# 04-ANDStatusLed.net
KiCad netlist of a schematic drawn in Altium Designer
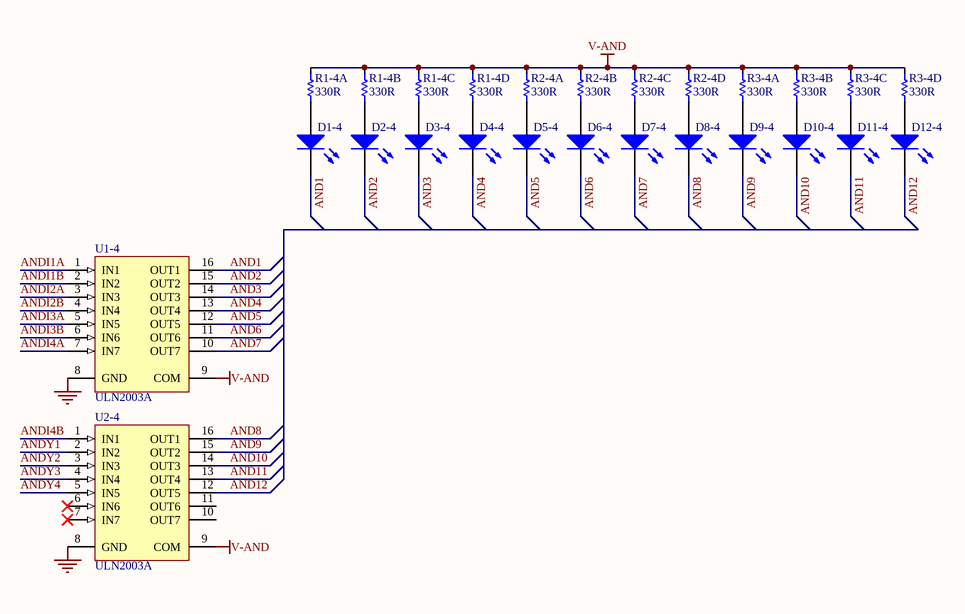
[diagram p0: 04-ANDStatusLed.SchDoc]

(export (version "E")
  (design (tool "Eeschema 10.0.6"))
  (components
    (comp (ref "D1-4")
      (value "LED")
      (footprint "LED-0805")
      (description "Typical RED, GREEN, YELLOW, AMBER GaAs LED")
      (fields (field (name "PUBLISHER") "Altium Limited"))
      (libsource (lib "Miscellaneous Devices") (part "LED2"))
    )
    (comp (ref "D2-4")
      (value "LED")
      (footprint "LED-0805")
      (description "Typical RED, GREEN, YELLOW, AMBER GaAs LED")
      (fields (field (name "PUBLISHER") "Altium Limited"))
      (libsource (lib "Miscellaneous Devices") (part "LED2"))
    )
    (comp (ref "D3-4")
      (value "LED")
      (footprint "LED-0805")
      (description "Typical RED, GREEN, YELLOW, AMBER GaAs LED")
      (fields (field (name "PUBLISHER") "Altium Limited"))
      (libsource (lib "Miscellaneous Devices") (part "LED2"))
    )
    (comp (ref "D4-4")
      (value "LED")
      (footprint "LED-0805")
      (description "Typical RED, GREEN, YELLOW, AMBER GaAs LED")
      (fields (field (name "PUBLISHER") "Altium Limited"))
      (libsource (lib "Miscellaneous Devices") (part "LED2"))
    )
    (comp (ref "D5-4")
      (value "LED")
      (footprint "LED-0805")
      (description "Typical RED, GREEN, YELLOW, AMBER GaAs LED")
      (fields (field (name "PUBLISHER") "Altium Limited"))
      (libsource (lib "Miscellaneous Devices") (part "LED2"))
    )
    (comp (ref "D6-4")
      (value "LED")
      (footprint "LED-0805")
      (description "Typical RED, GREEN, YELLOW, AMBER GaAs LED")
      (fields (field (name "PUBLISHER") "Altium Limited"))
      (libsource (lib "Miscellaneous Devices") (part "LED2"))
    )
    (comp (ref "D7-4")
      (value "LED")
      (footprint "LED-0805")
      (description "Typical RED, GREEN, YELLOW, AMBER GaAs LED")
      (fields (field (name "PUBLISHER") "Altium Limited"))
      (libsource (lib "Miscellaneous Devices") (part "LED2"))
    )
    (comp (ref "D8-4")
      (value "LED")
      (footprint "LED-0805")
      (description "Typical RED, GREEN, YELLOW, AMBER GaAs LED")
      (fields (field (name "PUBLISHER") "Altium Limited"))
      (libsource (lib "Miscellaneous Devices") (part "LED2"))
    )
    (comp (ref "D9-4")
      (value "LED")
      (footprint "LED-0805")
      (description "Typical RED, GREEN, YELLOW, AMBER GaAs LED")
      (fields (field (name "PUBLISHER") "Altium Limited"))
      (libsource (lib "Miscellaneous Devices") (part "LED2"))
    )
    (comp (ref "D10-4")
      (value "LED")
      (footprint "LED-0805")
      (description "Typical RED, GREEN, YELLOW, AMBER GaAs LED")
      (fields (field (name "PUBLISHER") "Altium Limited"))
      (libsource (lib "Miscellaneous Devices") (part "LED2"))
    )
    (comp (ref "D11-4")
      (value "LED")
      (footprint "LED-0805")
      (description "Typical RED, GREEN, YELLOW, AMBER GaAs LED")
      (fields (field (name "PUBLISHER") "Altium Limited"))
      (libsource (lib "Miscellaneous Devices") (part "LED2"))
    )
    (comp (ref "D12-4")
      (value "LED")
      (footprint "LED-0805")
      (description "Typical RED, GREEN, YELLOW, AMBER GaAs LED")
      (fields (field (name "PUBLISHER") "Altium Limited"))
      (libsource (lib "Miscellaneous Devices") (part "LED2"))
    )
    (comp (ref "R1-4")
      (value "330R")
      (footprint "R-Array-0603-4")
      (description "RES ARRAY 4 RES 330 OHM 1206")
      (fields
        (field (name "DIGI-KEY PART NUMBER") "Y9331TR-ND")
        (field (name "MANUFACTURER") "Panasonic Electronic Components")
      )
      (libsource (lib "Dlib") (part "Res Array 4"))
    )
    (comp (ref "R2-4")
      (value "330R")
      (footprint "R-Array-0603-4")
      (description "RES ARRAY 4 RES 330 OHM 1206")
      (fields
        (field (name "DIGI-KEY PART NUMBER") "Y9331TR-ND")
        (field (name "MANUFACTURER") "Panasonic Electronic Components")
      )
      (libsource (lib "Dlib") (part "Res Array 4"))
    )
    (comp (ref "R3-4")
      (value "330R")
      (footprint "R-Array-0603-4")
      (description "RES ARRAY 4 RES 330 OHM 1206")
      (fields
        (field (name "DIGI-KEY PART NUMBER") "Y9331TR-ND")
        (field (name "MANUFACTURER") "Panasonic Electronic Components")
      )
      (libsource (lib "Dlib") (part "Res Array 4"))
    )
    (comp (ref "U1-4")
      (value "ULN2003A")
      (footprint "SOIC-16")
      (description "High-Voltage, High-Current Darlington Array")
      (fields (field (name "PUBLISHER") "Altium Limited"))
      (libsource (lib "Allegro Interface Darlington Driver") (part "ULN2003A"))
    )
    (comp (ref "U2-4")
      (value "ULN2003A")
      (footprint "SOIC-16")
      (description "High-Voltage, High-Current Darlington Array")
      (fields (field (name "PUBLISHER") "Altium Limited"))
      (libsource (lib "Allegro Interface Darlington Driver") (part "ULN2003A"))
    )
  )
  (nets
    (net (code "1") (name "/AND1") (class "Default")
      (node (ref "D1-4") (pin "2") (pinfunction "K_2") (pintype "passive"))
      (node (ref "U1-4") (pin "16") (pinfunction "OUT1_16") (pintype "open_collector"))
    )
    (net (code "2") (name "/AND2") (class "Default")
      (node (ref "D2-4") (pin "2") (pinfunction "K_2") (pintype "passive"))
      (node (ref "U1-4") (pin "15") (pinfunction "OUT2_15") (pintype "open_collector"))
    )
    (net (code "3") (name "/AND3") (class "Default")
      (node (ref "D3-4") (pin "2") (pinfunction "K_2") (pintype "passive"))
      (node (ref "U1-4") (pin "14") (pinfunction "OUT3_14") (pintype "open_collector"))
    )
    (net (code "4") (name "/AND4") (class "Default")
      (node (ref "D4-4") (pin "2") (pinfunction "K_2") (pintype "passive"))
      (node (ref "U1-4") (pin "13") (pinfunction "OUT4_13") (pintype "open_collector"))
    )
    (net (code "5") (name "/AND5") (class "Default")
      (node (ref "D5-4") (pin "2") (pinfunction "K_2") (pintype "passive"))
      (node (ref "U1-4") (pin "12") (pinfunction "OUT5_12") (pintype "open_collector"))
    )
    (net (code "6") (name "/AND6") (class "Default")
      (node (ref "D6-4") (pin "2") (pinfunction "K_2") (pintype "passive"))
      (node (ref "U1-4") (pin "11") (pinfunction "OUT6_11") (pintype "open_collector"))
    )
    (net (code "7") (name "/AND7") (class "Default")
      (node (ref "D7-4") (pin "2") (pinfunction "K_2") (pintype "passive"))
      (node (ref "U1-4") (pin "10") (pinfunction "OUT7_10") (pintype "open_collector"))
    )
    (net (code "8") (name "/AND8") (class "Default")
      (node (ref "D8-4") (pin "2") (pinfunction "K_2") (pintype "passive"))
      (node (ref "U2-4") (pin "16") (pinfunction "OUT1_16") (pintype "open_collector"))
    )
    (net (code "9") (name "/AND9") (class "Default")
      (node (ref "D9-4") (pin "2") (pinfunction "K_2") (pintype "passive"))
      (node (ref "U2-4") (pin "15") (pinfunction "OUT2_15") (pintype "open_collector"))
    )
    (net (code "10") (name "/AND10") (class "Default")
      (node (ref "D10-4") (pin "2") (pinfunction "K_2") (pintype "passive"))
      (node (ref "U2-4") (pin "14") (pinfunction "OUT3_14") (pintype "open_collector"))
    )
    (net (code "11") (name "/AND11") (class "Default")
      (node (ref "D11-4") (pin "2") (pinfunction "K_2") (pintype "passive"))
      (node (ref "U2-4") (pin "13") (pinfunction "OUT4_13") (pintype "open_collector"))
    )
    (net (code "12") (name "/AND12") (class "Default")
      (node (ref "D12-4") (pin "2") (pinfunction "K_2") (pintype "passive"))
      (node (ref "U2-4") (pin "12") (pinfunction "OUT5_12") (pintype "open_collector"))
    )
    (net (code "13") (name "/ANDI1A") (class "Default")
      (node (ref "U1-4") (pin "1") (pinfunction "IN1_1") (pintype "input"))
    )
    (net (code "14") (name "/ANDI1B") (class "Default")
      (node (ref "U1-4") (pin "2") (pinfunction "IN2_2") (pintype "input"))
    )
    (net (code "15") (name "/ANDI2A") (class "Default")
      (node (ref "U1-4") (pin "3") (pinfunction "IN3_3") (pintype "input"))
    )
    (net (code "16") (name "/ANDI2B") (class "Default")
      (node (ref "U1-4") (pin "4") (pinfunction "IN4_4") (pintype "input"))
    )
    (net (code "17") (name "/ANDI3A") (class "Default")
      (node (ref "U1-4") (pin "5") (pinfunction "IN5_5") (pintype "input"))
    )
    (net (code "18") (name "/ANDI3B") (class "Default")
      (node (ref "U1-4") (pin "6") (pinfunction "IN6_6") (pintype "input"))
    )
    (net (code "19") (name "/ANDI4A") (class "Default")
      (node (ref "U1-4") (pin "7") (pinfunction "IN7_7") (pintype "input"))
    )
    (net (code "20") (name "/ANDI4B") (class "Default")
      (node (ref "U2-4") (pin "1") (pinfunction "IN1_1") (pintype "input"))
    )
    (net (code "21") (name "/ANDY1") (class "Default")
      (node (ref "U2-4") (pin "2") (pinfunction "IN2_2") (pintype "input"))
    )
    (net (code "22") (name "/ANDY2") (class "Default")
      (node (ref "U2-4") (pin "3") (pinfunction "IN3_3") (pintype "input"))
    )
    (net (code "23") (name "/ANDY3") (class "Default")
      (node (ref "U2-4") (pin "4") (pinfunction "IN4_4") (pintype "input"))
    )
    (net (code "24") (name "/ANDY4") (class "Default")
      (node (ref "U2-4") (pin "5") (pinfunction "IN5_5") (pintype "input"))
    )
    (net (code "25") (name "GND") (class "Default")
      (node (ref "U1-4") (pin "8") (pinfunction "GND_8") (pintype "power_in"))
      (node (ref "U2-4") (pin "8") (pinfunction "GND_8") (pintype "power_in"))
    )
    (net (code "26") (name "Net-(D1-4-A)") (class "Default")
      (node (ref "D1-4") (pin "1") (pinfunction "A_1") (pintype "passive"))
      (node (ref "R1-4") (pin "1") (pinfunction "1_1") (pintype "passive"))
    )
    (net (code "27") (name "Net-(D2-4-A)") (class "Default")
      (node (ref "D2-4") (pin "1") (pinfunction "A_1") (pintype "passive"))
      (node (ref "R1-4") (pin "3") (pinfunction "1_3") (pintype "passive"))
    )
    (net (code "28") (name "Net-(D3-4-A)") (class "Default")
      (node (ref "D3-4") (pin "1") (pinfunction "A_1") (pintype "passive"))
      (node (ref "R1-4") (pin "5") (pinfunction "1_5") (pintype "passive"))
    )
    (net (code "29") (name "Net-(D4-4-A)") (class "Default")
      (node (ref "D4-4") (pin "1") (pinfunction "A_1") (pintype "passive"))
      (node (ref "R1-4") (pin "7") (pinfunction "1_7") (pintype "passive"))
    )
    (net (code "30") (name "Net-(D5-4-A)") (class "Default")
      (node (ref "D5-4") (pin "1") (pinfunction "A_1") (pintype "passive"))
      (node (ref "R2-4") (pin "1") (pinfunction "1_1") (pintype "passive"))
    )
    (net (code "31") (name "Net-(D6-4-A)") (class "Default")
      (node (ref "D6-4") (pin "1") (pinfunction "A_1") (pintype "passive"))
      (node (ref "R2-4") (pin "3") (pinfunction "1_3") (pintype "passive"))
    )
    (net (code "32") (name "Net-(D7-4-A)") (class "Default")
      (node (ref "D7-4") (pin "1") (pinfunction "A_1") (pintype "passive"))
      (node (ref "R2-4") (pin "5") (pinfunction "1_5") (pintype "passive"))
    )
    (net (code "33") (name "Net-(D8-4-A)") (class "Default")
      (node (ref "D8-4") (pin "1") (pinfunction "A_1") (pintype "passive"))
      (node (ref "R2-4") (pin "7") (pinfunction "1_7") (pintype "passive"))
    )
    (net (code "34") (name "Net-(D9-4-A)") (class "Default")
      (node (ref "D9-4") (pin "1") (pinfunction "A_1") (pintype "passive"))
      (node (ref "R3-4") (pin "1") (pinfunction "1_1") (pintype "passive"))
    )
    (net (code "35") (name "Net-(D10-4-A)") (class "Default")
      (node (ref "D10-4") (pin "1") (pinfunction "A_1") (pintype "passive"))
      (node (ref "R3-4") (pin "3") (pinfunction "1_3") (pintype "passive"))
    )
    (net (code "36") (name "Net-(D11-4-A)") (class "Default")
      (node (ref "D11-4") (pin "1") (pinfunction "A_1") (pintype "passive"))
      (node (ref "R3-4") (pin "5") (pinfunction "1_5") (pintype "passive"))
    )
    (net (code "37") (name "Net-(D12-4-A)") (class "Default")
      (node (ref "D12-4") (pin "1") (pinfunction "A_1") (pintype "passive"))
      (node (ref "R3-4") (pin "7") (pinfunction "1_7") (pintype "passive"))
    )
    (net (code "38") (name "V-AND") (class "Default")
      (node (ref "R1-4") (pin "2") (pinfunction "2_2") (pintype "passive"))
      (node (ref "R1-4") (pin "4") (pinfunction "2_4") (pintype "passive"))
      (node (ref "R1-4") (pin "6") (pinfunction "2_6") (pintype "passive"))
      (node (ref "R1-4") (pin "8") (pinfunction "2_8") (pintype "passive"))
      (node (ref "R2-4") (pin "2") (pinfunction "2_2") (pintype "passive"))
      (node (ref "R2-4") (pin "4") (pinfunction "2_4") (pintype "passive"))
      (node (ref "R2-4") (pin "6") (pinfunction "2_6") (pintype "passive"))
      (node (ref "R2-4") (pin "8") (pinfunction "2_8") (pintype "passive"))
      (node (ref "R3-4") (pin "2") (pinfunction "2_2") (pintype "passive"))
      (node (ref "R3-4") (pin "4") (pinfunction "2_4") (pintype "passive"))
      (node (ref "R3-4") (pin "6") (pinfunction "2_6") (pintype "passive"))
      (node (ref "R3-4") (pin "8") (pinfunction "2_8") (pintype "passive"))
      (node (ref "U1-4") (pin "9") (pinfunction "COM_9") (pintype "passive"))
      (node (ref "U2-4") (pin "9") (pinfunction "COM_9") (pintype "passive"))
    )
    (net (code "39") (name "unconnected-(U2-4-IN6-Pad6)") (class "Default")
      (node (ref "U2-4") (pin "6") (pinfunction "IN6_6") (pintype "input+no_connect"))
    )
    (net (code "40") (name "unconnected-(U2-4-IN7-Pad7)") (class "Default")
      (node (ref "U2-4") (pin "7") (pinfunction "IN7_7") (pintype "input+no_connect"))
    )
    (net (code "41") (name "unconnected-(U2-4-OUT6-Pad11)") (class "Default")
      (node (ref "U2-4") (pin "11") (pinfunction "OUT6_11") (pintype "open_collector"))
    )
    (net (code "42") (name "unconnected-(U2-4-OUT7-Pad10)") (class "Default")
      (node (ref "U2-4") (pin "10") (pinfunction "OUT7_10") (pintype "open_collector"))
    )
  )
)
